# Peripherals.net
KiCad netlist of a schematic drawn in Altium Designer
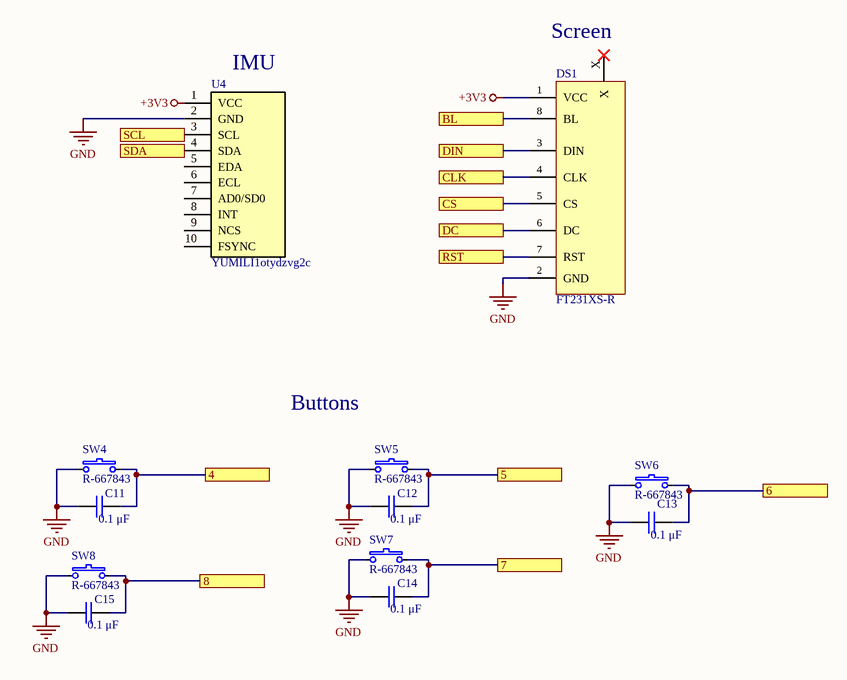
[diagram p0: Peripherals.SchDoc]

(export (version "E")
  (design (tool "Eeschema 10.0.6"))
  (components
    (comp (ref "C11")
      (value "0.1 μF")
      (footprint "Capacitor 0603")
      (description "Capacitor 0.1 μF")
      (fields
        (field (name "MANUFACTURER") "Samsung Electro-Mechanics")
        (field (name "MANUFACTURER PART NUMBER") "CL10B104KB8NNWC")
      )
      (libsource (lib "Schlib1") (part "0.1 μF 0603"))
    )
    (comp (ref "C12")
      (value "0.1 μF")
      (footprint "Capacitor 0603")
      (description "Capacitor 0.1 μF")
      (fields
        (field (name "MANUFACTURER") "Samsung Electro-Mechanics")
        (field (name "MANUFACTURER PART NUMBER") "CL10B104KB8NNWC")
      )
      (libsource (lib "Schlib1") (part "0.1 μF 0603"))
    )
    (comp (ref "C13")
      (value "0.1 μF")
      (footprint "Capacitor 0603")
      (description "Capacitor 0.1 μF")
      (fields
        (field (name "MANUFACTURER") "Samsung Electro-Mechanics")
        (field (name "MANUFACTURER PART NUMBER") "CL10B104KB8NNWC")
      )
      (libsource (lib "Schlib1") (part "0.1 μF 0603"))
    )
    (comp (ref "C14")
      (value "0.1 μF")
      (footprint "Capacitor 0603")
      (description "Capacitor 0.1 μF")
      (fields
        (field (name "MANUFACTURER") "Samsung Electro-Mechanics")
        (field (name "MANUFACTURER PART NUMBER") "CL10B104KB8NNWC")
      )
      (libsource (lib "Schlib1") (part "0.1 μF 0603"))
    )
    (comp (ref "C15")
      (value "0.1 μF")
      (footprint "Capacitor 0603")
      (description "Capacitor 0.1 μF")
      (fields
        (field (name "MANUFACTURER") "Samsung Electro-Mechanics")
        (field (name "MANUFACTURER PART NUMBER") "CL10B104KB8NNWC")
      )
      (libsource (lib "Schlib1") (part "0.1 μF 0603"))
    )
    (comp (ref "DS1")
      (value "FT231XS-R")
      (footprint "Screen")
      (description "240×320, General 2.4inch LCD Display Module, 65K RGB")
      (fields (field (name "MANUFACTURER") "FTDI, Future Technology Devices International Ltd"))
      (libsource (lib "SchLib") (part "LCD-screen"))
    )
    (comp (ref "SW4")
      (value "R-667843")
      (footprint "R-667843")
      (description "SWITCH TACTILE SPST-NO 0.05A 12V")
      (fields (field (name "MANUFACTURER") "Mitsumi Electric Company Ltd"))
      (libsource (lib "Schlib1") (part "R-667843"))
    )
    (comp (ref "SW5")
      (value "R-667843")
      (footprint "R-667843")
      (description "SWITCH TACTILE SPST-NO 0.05A 12V")
      (fields (field (name "MANUFACTURER") "Mitsumi Electric Company Ltd"))
      (libsource (lib "Schlib1") (part "R-667843"))
    )
    (comp (ref "SW6")
      (value "R-667843")
      (footprint "R-667843")
      (description "SWITCH TACTILE SPST-NO 0.05A 12V")
      (fields (field (name "MANUFACTURER") "Mitsumi Electric Company Ltd"))
      (libsource (lib "Schlib1") (part "R-667843"))
    )
    (comp (ref "SW7")
      (value "R-667843")
      (footprint "R-667843")
      (description "SWITCH TACTILE SPST-NO 0.05A 12V")
      (fields (field (name "MANUFACTURER") "Mitsumi Electric Company Ltd"))
      (libsource (lib "Schlib1") (part "R-667843"))
    )
    (comp (ref "SW8")
      (value "R-667843")
      (footprint "R-667843")
      (description "SWITCH TACTILE SPST-NO 0.05A 12V")
      (fields (field (name "MANUFACTURER") "Mitsumi Electric Company Ltd"))
      (libsource (lib "Schlib1") (part "R-667843"))
    )
    (comp (ref "U4")
      (value "YUMILI1otydzvg2c")
      (footprint "GY-9250")
      (description "YUMILI Gyroskopmodul MPU-9250 GY-9250 9-axel 16-bitars")
      (fields (field (name "MANUFACTURER") "YUMILI"))
      (libsource (lib "SchLib") (part "GY-9250"))
    )
  )
  (nets
    (net (code "1") (name "+3V3") (class "Default")
      (node (ref "DS1") (pin "1") (pinfunction "VCC_1") (pintype "passive"))
      (node (ref "U4") (pin "1") (pinfunction "VCC_1") (pintype "passive"))
    )
    (net (code "2") (name "/4") (class "Default")
      (node (ref "C11") (pin "B") (pinfunction "B_B") (pintype "passive"))
      (node (ref "SW4") (pin "B") (pinfunction "B_B") (pintype "passive"))
    )
    (net (code "3") (name "/5") (class "Default")
      (node (ref "C12") (pin "B") (pinfunction "B_B") (pintype "passive"))
      (node (ref "SW5") (pin "B") (pinfunction "B_B") (pintype "passive"))
    )
    (net (code "4") (name "/6") (class "Default")
      (node (ref "C13") (pin "B") (pinfunction "B_B") (pintype "passive"))
      (node (ref "SW6") (pin "B") (pinfunction "B_B") (pintype "passive"))
    )
    (net (code "5") (name "/7") (class "Default")
      (node (ref "C14") (pin "B") (pinfunction "B_B") (pintype "passive"))
      (node (ref "SW7") (pin "B") (pinfunction "B_B") (pintype "passive"))
    )
    (net (code "6") (name "/8") (class "Default")
      (node (ref "C15") (pin "B") (pinfunction "B_B") (pintype "passive"))
      (node (ref "SW8") (pin "B") (pinfunction "B_B") (pintype "passive"))
    )
    (net (code "7") (name "/BL") (class "Default")
      (node (ref "DS1") (pin "8") (pinfunction "BL_8") (pintype "passive"))
    )
    (net (code "8") (name "/CLK") (class "Default")
      (node (ref "DS1") (pin "4") (pinfunction "CLK_4") (pintype "passive"))
    )
    (net (code "9") (name "/CS") (class "Default")
      (node (ref "DS1") (pin "5") (pinfunction "CS_5") (pintype "passive"))
    )
    (net (code "10") (name "/DC") (class "Default")
      (node (ref "DS1") (pin "6") (pinfunction "DC_6") (pintype "passive"))
    )
    (net (code "11") (name "/DIN") (class "Default")
      (node (ref "DS1") (pin "3") (pinfunction "DIN_3") (pintype "passive"))
    )
    (net (code "12") (name "/RST") (class "Default")
      (node (ref "DS1") (pin "7") (pinfunction "RST_7") (pintype "passive"))
    )
    (net (code "13") (name "/SCL") (class "Default")
      (node (ref "U4") (pin "3") (pinfunction "SCL_3") (pintype "passive"))
    )
    (net (code "14") (name "/SDA") (class "Default")
      (node (ref "U4") (pin "4") (pinfunction "SDA_4") (pintype "passive"))
    )
    (net (code "15") (name "GND") (class "Default")
      (node (ref "C11") (pin "A") (pinfunction "A_A") (pintype "passive"))
      (node (ref "C12") (pin "A") (pinfunction "A_A") (pintype "passive"))
      (node (ref "C13") (pin "A") (pinfunction "A_A") (pintype "passive"))
      (node (ref "C14") (pin "A") (pinfunction "A_A") (pintype "passive"))
      (node (ref "C15") (pin "A") (pinfunction "A_A") (pintype "passive"))
      (node (ref "DS1") (pin "2") (pinfunction "GND_2") (pintype "passive"))
      (node (ref "SW4") (pin "A") (pinfunction "A_A") (pintype "passive"))
      (node (ref "SW5") (pin "A") (pinfunction "A_A") (pintype "passive"))
      (node (ref "SW6") (pin "A") (pinfunction "A_A") (pintype "passive"))
      (node (ref "SW7") (pin "A") (pinfunction "A_A") (pintype "passive"))
      (node (ref "SW8") (pin "A") (pinfunction "A_A") (pintype "passive"))
      (node (ref "U4") (pin "2") (pinfunction "GND_2") (pintype "passive"))
    )
    (net (code "16") (name "unconnected-(DS1-PadX)") (class "Default")
      (node (ref "DS1") (pin "X") (pinfunction "X_X") (pintype "passive+no_connect"))
    )
    (net (code "17") (name "unconnected-(U4-AD0{slash}SD0-Pad7)") (class "Default")
      (node (ref "U4") (pin "7") (pinfunction "AD0/SD0_7") (pintype "passive"))
    )
    (net (code "18") (name "unconnected-(U4-ECL-Pad6)") (class "Default")
      (node (ref "U4") (pin "6") (pinfunction "ECL_6") (pintype "passive"))
    )
    (net (code "19") (name "unconnected-(U4-EDA-Pad5)") (class "Default")
      (node (ref "U4") (pin "5") (pinfunction "EDA_5") (pintype "passive"))
    )
    (net (code "20") (name "unconnected-(U4-FSYNC-Pad10)") (class "Default")
      (node (ref "U4") (pin "10") (pinfunction "FSYNC_10") (pintype "passive"))
    )
    (net (code "21") (name "unconnected-(U4-INT-Pad8)") (class "Default")
      (node (ref "U4") (pin "8") (pinfunction "INT_8") (pintype "passive"))
    )
    (net (code "22") (name "unconnected-(U4-NCS-Pad9)") (class "Default")
      (node (ref "U4") (pin "9") (pinfunction "NCS_9") (pintype "passive"))
    )
  )
)
